# attinier85-light-sensor-shield-mk-1_0.net
KiCad netlist of a schematic drawn in EAGLE
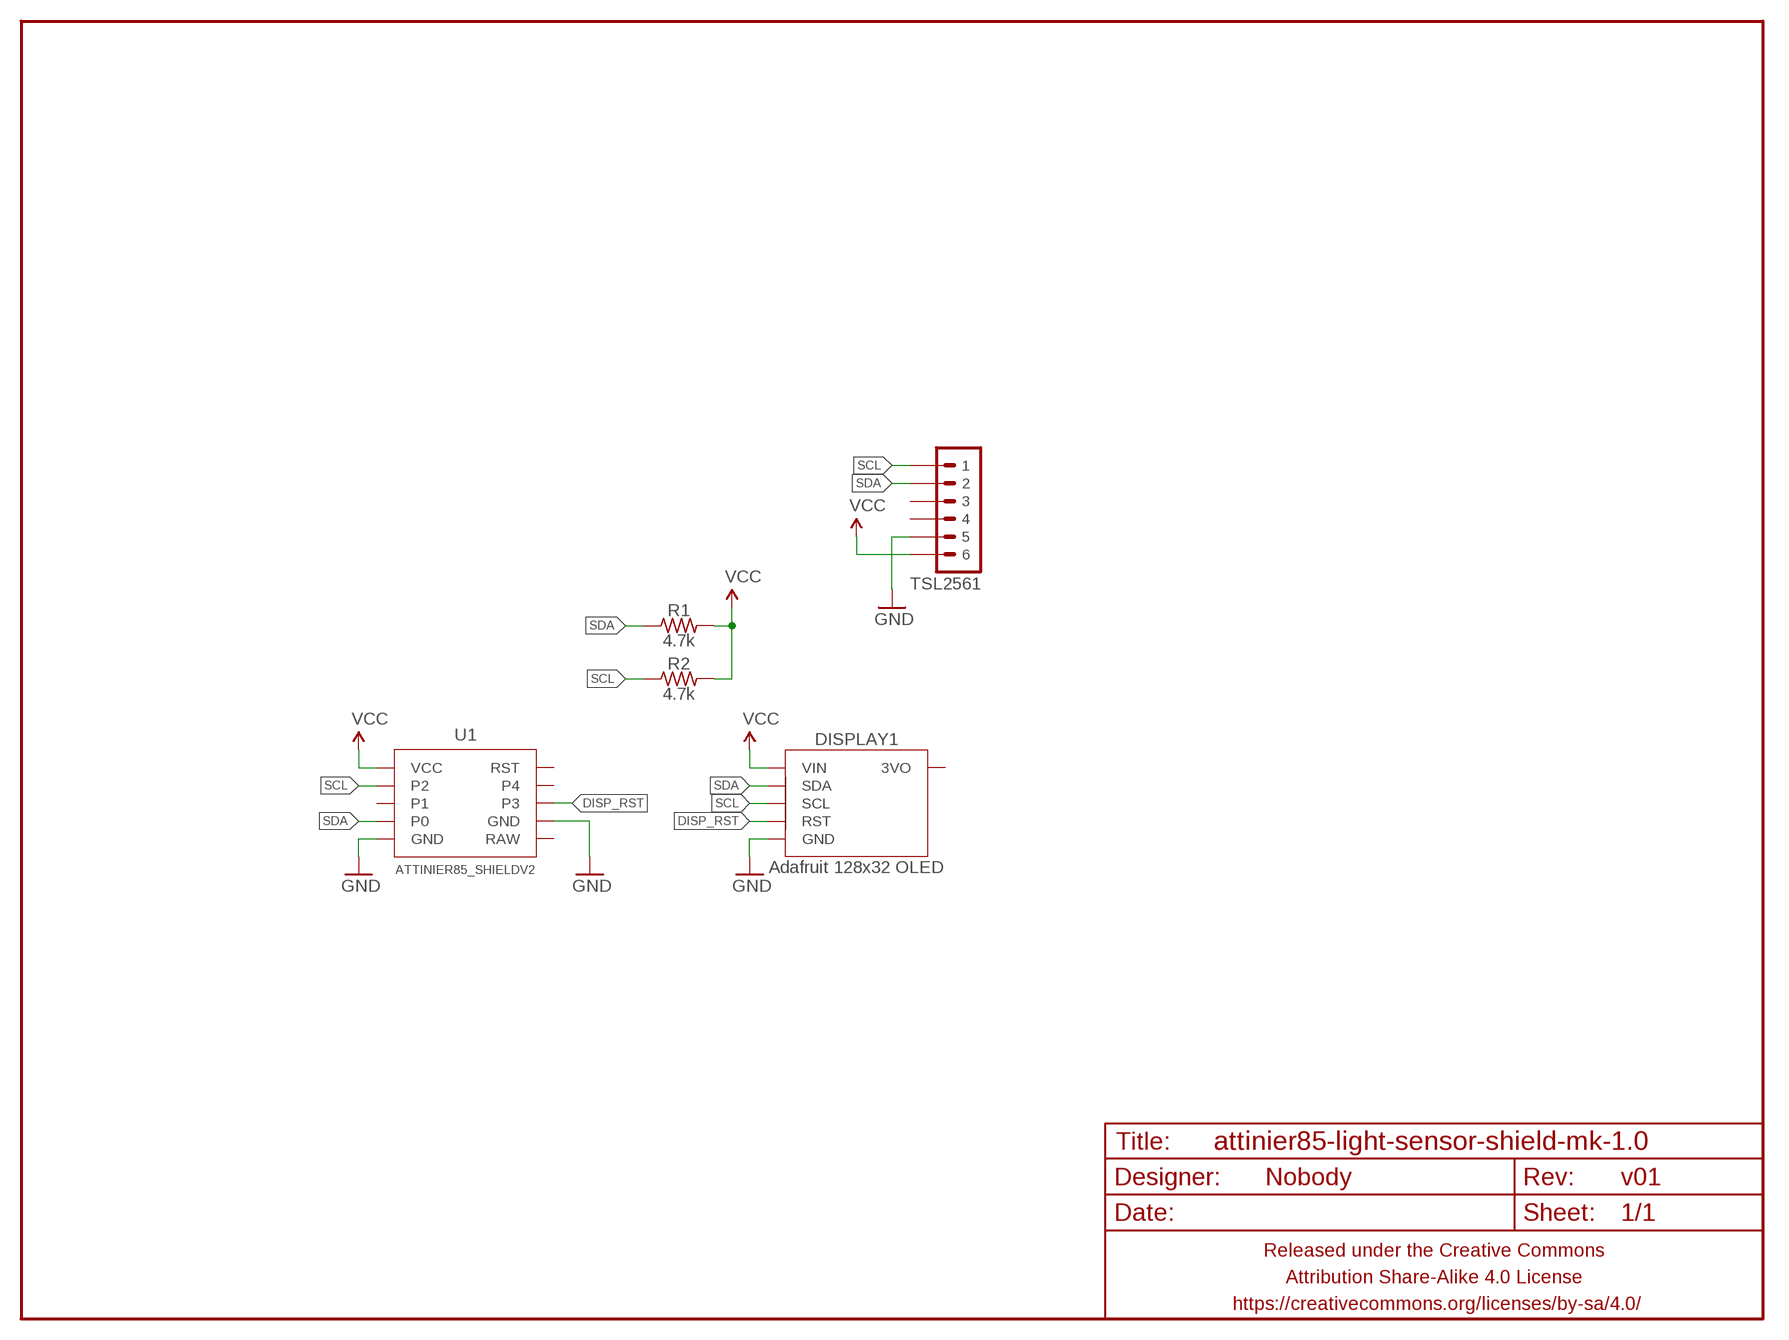
[diagram p0: schematic, sheet 1]

(export (version "E")
  (design (tool "Eeschema 10.0.6"))
  (components
    (comp (ref "DISPLAY1")
      (value "Adafruit 128x32 OLED")
      (footprint "eagle-import:ADAFRUIT_128X32_OLED_I2C_CLOSER_NOHOLES")
      (libsource (lib "eagle-import") (part "ADAFRUIT_128X32_OLED_I2CNOHOLES"))
    )
    (comp (ref "FRAME1")
      (value "FRAME-LETTERNO_PACKAGE")
      (footprint "eagle-import:DUMMY")
      (fields (field (name "DESIGNER") "Nobody"))
      (libsource (lib "eagle-import") (part "FRAME-LETTERNO_PACKAGE"))
    )
    (comp (ref "R1")
      (value "4.7k")
      (footprint "eagle-import:RESISTOR-AXIAL-PTH-7.62MM")
      (libsource (lib "eagle-import") (part "RESISTORPTH-AXIAL-7.62MM"))
    )
    (comp (ref "R2")
      (value "4.7k")
      (footprint "eagle-import:RESISTOR-AXIAL-PTH-7.62MM")
      (libsource (lib "eagle-import") (part "RESISTORPTH-AXIAL-7.62MM"))
    )
    (comp (ref "TSL2561")
      (value "M06CLOSER")
      (footprint "eagle-import:1X06_CLOSER")
      (libsource (lib "eagle-import") (part "M06CLOSER"))
    )
    (comp (ref "U1")
      (value "ATTINIER85_SHIELDV2")
      (footprint "eagle-import:ATTINIER85_SHIELD_V2")
      (libsource (lib "eagle-import") (part "ATTINIER85_SHIELDV2"))
    )
  )
  (nets
    (net (code "1") (name "DISP_RST") (class "Default")
      (node (ref "DISPLAY1") (pin "RST") (pinfunction "RST_RST") (pintype "bidirectional"))
      (node (ref "U1") (pin "3") (pinfunction "P3_3") (pintype "bidirectional"))
    )
    (net (code "2") (name "GND") (class "Default")
      (node (ref "DISPLAY1") (pin "GND") (pinfunction "GND_GND") (pintype "bidirectional"))
      (node (ref "TSL2561") (pin "5") (pinfunction "5_5") (pintype "passive"))
      (node (ref "U1") (pin "GND@1") (pinfunction "GND_GND@1") (pintype "bidirectional"))
      (node (ref "U1") (pin "GND@2") (pinfunction "GND_GND@2") (pintype "bidirectional"))
    )
    (net (code "3") (name "SCL") (class "Default")
      (node (ref "DISPLAY1") (pin "SCL") (pinfunction "SCL_SCL") (pintype "bidirectional"))
      (node (ref "R2") (pin "P$1") (pinfunction "1_P$1") (pintype "passive"))
      (node (ref "TSL2561") (pin "1") (pinfunction "1_1") (pintype "passive"))
      (node (ref "U1") (pin "2") (pinfunction "P2_2") (pintype "bidirectional"))
    )
    (net (code "4") (name "SDA") (class "Default")
      (node (ref "DISPLAY1") (pin "SDA") (pinfunction "SDA_SDA") (pintype "bidirectional"))
      (node (ref "R1") (pin "P$1") (pinfunction "1_P$1") (pintype "passive"))
      (node (ref "TSL2561") (pin "2") (pinfunction "2_2") (pintype "passive"))
      (node (ref "U1") (pin "0") (pinfunction "P0_0") (pintype "bidirectional"))
    )
    (net (code "5") (name "VCC") (class "Default")
      (node (ref "DISPLAY1") (pin "VIN") (pinfunction "VIN_VIN") (pintype "bidirectional"))
      (node (ref "R1") (pin "P$2") (pinfunction "2_P$2") (pintype "passive"))
      (node (ref "R2") (pin "P$2") (pinfunction "2_P$2") (pintype "passive"))
      (node (ref "TSL2561") (pin "6") (pinfunction "6_6") (pintype "passive"))
      (node (ref "U1") (pin "VCC") (pinfunction "VCC_VCC") (pintype "bidirectional"))
    )
    (net (code "6") (name "unconnected-(DISPLAY1-Pad3VO)") (class "Default")
      (node (ref "DISPLAY1") (pin "3VO") (pinfunction "3VO_3VO") (pintype "bidirectional"))
    )
    (net (code "7") (name "unconnected-(TSL2561-Pad3)") (class "Default")
      (node (ref "TSL2561") (pin "3") (pinfunction "3_3") (pintype "passive"))
    )
    (net (code "8") (name "unconnected-(TSL2561-Pad4)") (class "Default")
      (node (ref "TSL2561") (pin "4") (pinfunction "4_4") (pintype "passive"))
    )
    (net (code "9") (name "unconnected-(U1-P1-Pad1)") (class "Default")
      (node (ref "U1") (pin "1") (pinfunction "P1_1") (pintype "bidirectional"))
    )
    (net (code "10") (name "unconnected-(U1-P4-Pad4)") (class "Default")
      (node (ref "U1") (pin "4") (pinfunction "P4_4") (pintype "bidirectional"))
    )
    (net (code "11") (name "unconnected-(U1-PadRAW)") (class "Default")
      (node (ref "U1") (pin "RAW") (pinfunction "RAW_RAW") (pintype "bidirectional"))
    )
    (net (code "12") (name "unconnected-(U1-PadRST)") (class "Default")
      (node (ref "U1") (pin "RST") (pinfunction "RST_RST") (pintype "bidirectional"))
    )
  )
)
